# tssop28breakout.net
KiCad netlist of a schematic drawn in EAGLE
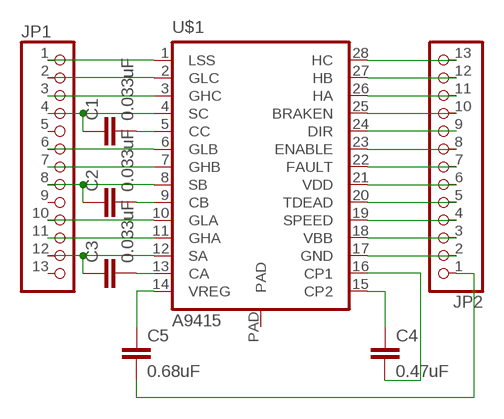
[diagram p0: schematic, sheet 1]

(export (version "E")
  (design (tool "Eeschema 10.0.6"))
  (components
    (comp (ref "C1")
      (value "0.033uF")
      (footprint "eagle-import:C0805")
      (libsource (lib "eagle-import") (part "C-EUC0805"))
    )
    (comp (ref "C2")
      (value "0.033uF")
      (footprint "eagle-import:C0805")
      (libsource (lib "eagle-import") (part "C-EUC0805"))
    )
    (comp (ref "C3")
      (value "0.033uF")
      (footprint "eagle-import:C0805")
      (libsource (lib "eagle-import") (part "C-EUC0805"))
    )
    (comp (ref "C4")
      (value "0.47uF")
      (footprint "eagle-import:C0805")
      (libsource (lib "eagle-import") (part "C-EUC0805"))
    )
    (comp (ref "C5")
      (value "0.68uF")
      (footprint "eagle-import:C0805")
      (libsource (lib "eagle-import") (part "C-EUC0805"))
    )
    (comp (ref "JP1")
      (value "PINHD-1X13_BIG")
      (footprint "eagle-import:1X13-BIG")
      (libsource (lib "eagle-import") (part "PINHD-1X13_BIG"))
    )
    (comp (ref "JP2")
      (value "PINHD-1X13_BIG")
      (footprint "eagle-import:1X13-BIG")
      (libsource (lib "eagle-import") (part "PINHD-1X13_BIG"))
    )
    (comp (ref "U$1")
      (value "A9415")
      (footprint "eagle-import:TSSOP28")
      (libsource (lib "eagle-import") (part "A9415"))
    )
  )
  (nets
    (net (code "1") (name "/PAD") (class "Default")
      (node (ref "U$1") (pin "PAD") (pinfunction "PAD_PAD") (pintype "power_in"))
    )
    (net (code "2") (name "Net-(C5-Pad2)") (class "Default")
      (node (ref "C5") (pin "2") (pinfunction "2_2") (pintype "passive"))
      (node (ref "JP2") (pin "1") (pinfunction "1_1") (pintype "passive"))
    )
    (net (code "3") (name "Net-(U$1-BRAKEN)") (class "Default")
      (node (ref "JP2") (pin "10") (pinfunction "10_10") (pintype "passive"))
      (node (ref "U$1") (pin "25") (pinfunction "BRAKEN_25") (pintype "bidirectional"))
    )
    (net (code "4") (name "Net-(U$1-CA)") (class "Default")
      (node (ref "C3") (pin "2") (pinfunction "2_2") (pintype "passive"))
      (node (ref "U$1") (pin "13") (pinfunction "CA_13") (pintype "output"))
    )
    (net (code "5") (name "Net-(U$1-CB)") (class "Default")
      (node (ref "C2") (pin "2") (pinfunction "2_2") (pintype "passive"))
      (node (ref "U$1") (pin "9") (pinfunction "CB_9") (pintype "output"))
    )
    (net (code "6") (name "Net-(U$1-CC)") (class "Default")
      (node (ref "C1") (pin "2") (pinfunction "2_2") (pintype "passive"))
      (node (ref "U$1") (pin "5") (pinfunction "CC_5") (pintype "output"))
    )
    (net (code "7") (name "Net-(U$1-CP1)") (class "Default")
      (node (ref "C4") (pin "2") (pinfunction "2_2") (pintype "passive"))
      (node (ref "U$1") (pin "16") (pinfunction "CP1_16") (pintype "input"))
    )
    (net (code "8") (name "Net-(U$1-CP2)") (class "Default")
      (node (ref "C4") (pin "1") (pinfunction "1_1") (pintype "passive"))
      (node (ref "U$1") (pin "15") (pinfunction "CP2_15") (pintype "passive"))
    )
    (net (code "9") (name "Net-(U$1-DIR)") (class "Default")
      (node (ref "JP2") (pin "9") (pinfunction "9_9") (pintype "passive"))
      (node (ref "U$1") (pin "24") (pinfunction "DIR_24") (pintype "input"))
    )
    (net (code "10") (name "Net-(U$1-ENABLE)") (class "Default")
      (node (ref "JP2") (pin "8") (pinfunction "8_8") (pintype "passive"))
      (node (ref "U$1") (pin "23") (pinfunction "ENABLE_23") (pintype "input"))
    )
    (net (code "11") (name "Net-(U$1-FAULT)") (class "Default")
      (node (ref "JP2") (pin "7") (pinfunction "7_7") (pintype "passive"))
      (node (ref "U$1") (pin "22") (pinfunction "FAULT_22") (pintype "output"))
    )
    (net (code "12") (name "Net-(U$1-GHA)") (class "Default")
      (node (ref "JP1") (pin "11") (pinfunction "11_11") (pintype "passive"))
      (node (ref "U$1") (pin "11") (pinfunction "GHA_11") (pintype "output"))
    )
    (net (code "13") (name "Net-(U$1-GHB)") (class "Default")
      (node (ref "JP1") (pin "7") (pinfunction "7_7") (pintype "passive"))
      (node (ref "U$1") (pin "7") (pinfunction "GHB_7") (pintype "output"))
    )
    (net (code "14") (name "Net-(U$1-GHC)") (class "Default")
      (node (ref "JP1") (pin "3") (pinfunction "3_3") (pintype "passive"))
      (node (ref "U$1") (pin "3") (pinfunction "GHC_3") (pintype "output"))
    )
    (net (code "15") (name "Net-(U$1-GLA)") (class "Default")
      (node (ref "JP1") (pin "10") (pinfunction "10_10") (pintype "passive"))
      (node (ref "U$1") (pin "10") (pinfunction "GLA_10") (pintype "output"))
    )
    (net (code "16") (name "Net-(U$1-GLB)") (class "Default")
      (node (ref "JP1") (pin "6") (pinfunction "6_6") (pintype "passive"))
      (node (ref "U$1") (pin "6") (pinfunction "GLB_6") (pintype "output"))
    )
    (net (code "17") (name "Net-(U$1-GLC)") (class "Default")
      (node (ref "JP1") (pin "2") (pinfunction "2_2") (pintype "passive"))
      (node (ref "U$1") (pin "2") (pinfunction "GLC_2") (pintype "output"))
    )
    (net (code "18") (name "Net-(U$1-GND)") (class "Default")
      (node (ref "JP2") (pin "2") (pinfunction "2_2") (pintype "passive"))
      (node (ref "U$1") (pin "17") (pinfunction "GND_17") (pintype "power_in"))
    )
    (net (code "19") (name "Net-(U$1-HA)") (class "Default")
      (node (ref "JP2") (pin "11") (pinfunction "11_11") (pintype "passive"))
      (node (ref "U$1") (pin "26") (pinfunction "HA_26") (pintype "input"))
    )
    (net (code "20") (name "Net-(U$1-HB)") (class "Default")
      (node (ref "JP2") (pin "12") (pinfunction "12_12") (pintype "passive"))
      (node (ref "U$1") (pin "27") (pinfunction "HB_27") (pintype "input"))
    )
    (net (code "21") (name "Net-(U$1-HC)") (class "Default")
      (node (ref "JP2") (pin "13") (pinfunction "13_13") (pintype "passive"))
      (node (ref "U$1") (pin "28") (pinfunction "HC_28") (pintype "input"))
    )
    (net (code "22") (name "Net-(U$1-LSS)") (class "Default")
      (node (ref "JP1") (pin "1") (pinfunction "1_1") (pintype "passive"))
      (node (ref "U$1") (pin "1") (pinfunction "LSS_1") (pintype "input"))
    )
    (net (code "23") (name "Net-(U$1-SA)") (class "Default")
      (node (ref "C3") (pin "1") (pinfunction "1_1") (pintype "passive"))
      (node (ref "JP1") (pin "12") (pinfunction "12_12") (pintype "passive"))
      (node (ref "U$1") (pin "12") (pinfunction "SA_12") (pintype "output"))
    )
    (net (code "24") (name "Net-(U$1-SB)") (class "Default")
      (node (ref "C2") (pin "1") (pinfunction "1_1") (pintype "passive"))
      (node (ref "JP1") (pin "8") (pinfunction "8_8") (pintype "passive"))
      (node (ref "U$1") (pin "8") (pinfunction "SB_8") (pintype "output"))
    )
    (net (code "25") (name "Net-(U$1-SC)") (class "Default")
      (node (ref "C1") (pin "1") (pinfunction "1_1") (pintype "passive"))
      (node (ref "JP1") (pin "4") (pinfunction "4_4") (pintype "passive"))
      (node (ref "U$1") (pin "4") (pinfunction "SC_4") (pintype "output"))
    )
    (net (code "26") (name "Net-(U$1-SPEED)") (class "Default")
      (node (ref "JP2") (pin "4") (pinfunction "4_4") (pintype "passive"))
      (node (ref "U$1") (pin "19") (pinfunction "SPEED_19") (pintype "input"))
    )
    (net (code "27") (name "Net-(U$1-TDEAD)") (class "Default")
      (node (ref "JP2") (pin "5") (pinfunction "5_5") (pintype "passive"))
      (node (ref "U$1") (pin "20") (pinfunction "TDEAD_20") (pintype "input"))
    )
    (net (code "28") (name "Net-(U$1-VBB)") (class "Default")
      (node (ref "JP2") (pin "3") (pinfunction "3_3") (pintype "passive"))
      (node (ref "U$1") (pin "18") (pinfunction "VBB_18") (pintype "power_in"))
    )
    (net (code "29") (name "Net-(U$1-VDD)") (class "Default")
      (node (ref "JP2") (pin "6") (pinfunction "6_6") (pintype "passive"))
      (node (ref "U$1") (pin "21") (pinfunction "VDD_21") (pintype "power_in"))
    )
    (net (code "30") (name "Net-(U$1-VREG)") (class "Default")
      (node (ref "C5") (pin "1") (pinfunction "1_1") (pintype "passive"))
      (node (ref "U$1") (pin "14") (pinfunction "VREG_14") (pintype "power_in"))
    )
    (net (code "31") (name "unconnected-(JP1-Pad5)") (class "Default")
      (node (ref "JP1") (pin "5") (pinfunction "5_5") (pintype "passive"))
    )
    (net (code "32") (name "unconnected-(JP1-Pad9)") (class "Default")
      (node (ref "JP1") (pin "9") (pinfunction "9_9") (pintype "passive"))
    )
    (net (code "33") (name "unconnected-(JP1-Pad13)") (class "Default")
      (node (ref "JP1") (pin "13") (pinfunction "13_13") (pintype "passive"))
    )
  )
)
